# Slave_Device.net
KiCad netlist of a schematic drawn in EAGLE
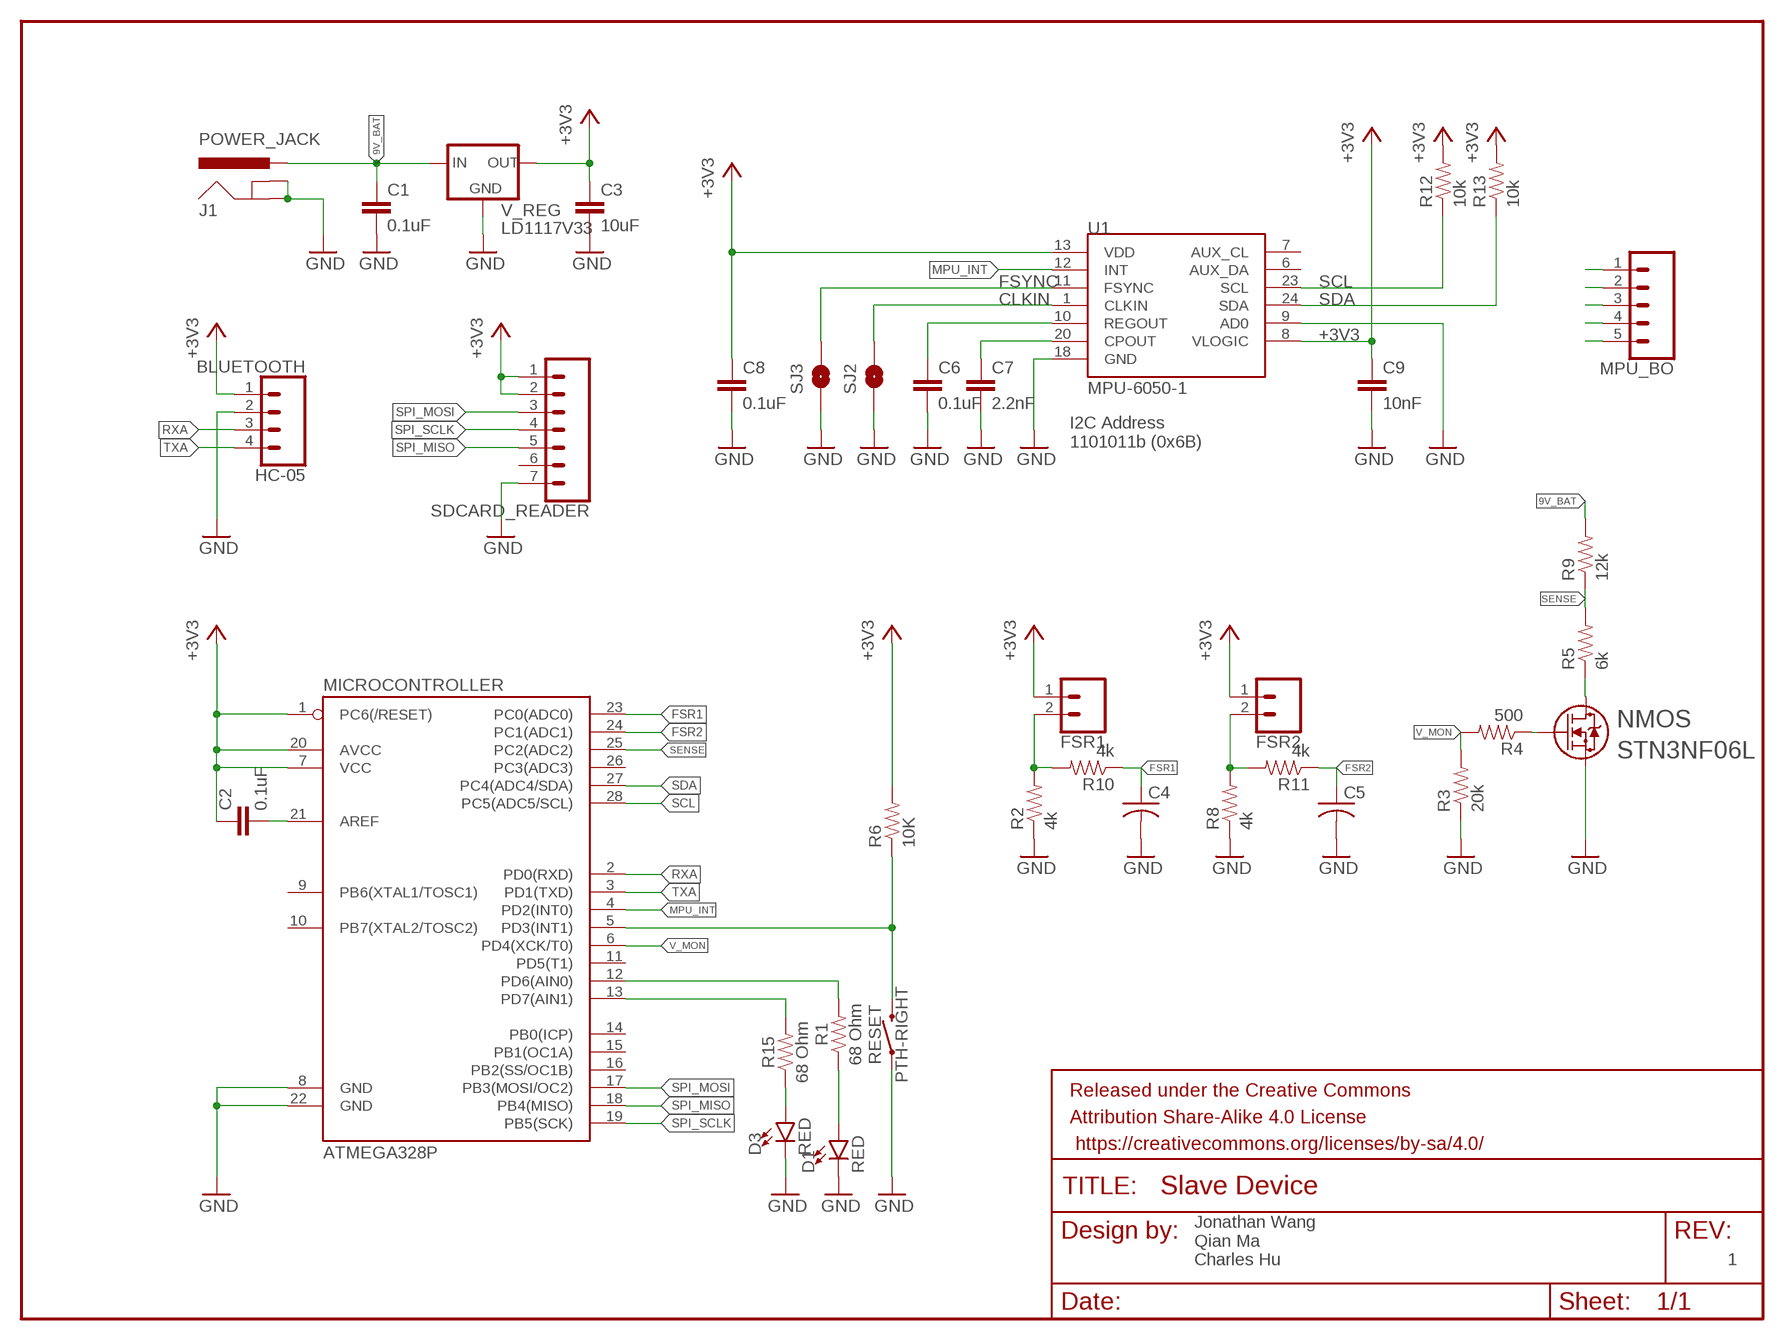
[diagram p0: schematic, sheet 1]

(export (version "E")
  (design (tool "Eeschema 10.0.6"))
  (components
    (comp (ref "C1")
      (value "0.1uF")
      (footprint "eagle-import:0603-CAP")
      (libsource (lib "eagle-import") (part "CAP0603-CAP"))
    )
    (comp (ref "C2")
      (value "0.1uF")
      (footprint "eagle-import:0603-CAP")
      (libsource (lib "eagle-import") (part "CAP0603-CAP"))
    )
    (comp (ref "C3")
      (value "10uF")
      (footprint "eagle-import:0603-CAP")
      (libsource (lib "eagle-import") (part "CAP0603-CAP"))
    )
    (comp (ref "C4")
      (value "C-US050-050X075")
      (footprint "eagle-import:C050-050X075")
      (libsource (lib "eagle-import") (part "C-US050-050X075"))
    )
    (comp (ref "C5")
      (value "C-US050-050X075")
      (footprint "eagle-import:C050-050X075")
      (libsource (lib "eagle-import") (part "C-US050-050X075"))
    )
    (comp (ref "C6")
      (value "0.1uF")
      (footprint "eagle-import:0603-CAP")
      (libsource (lib "eagle-import") (part "CAP0603-CAP"))
    )
    (comp (ref "C7")
      (value "2.2nF")
      (footprint "eagle-import:0603-CAP")
      (libsource (lib "eagle-import") (part "CAP0603-CAP"))
    )
    (comp (ref "C8")
      (value "0.1uF")
      (footprint "eagle-import:0603-CAP")
      (libsource (lib "eagle-import") (part "CAP0603-CAP"))
    )
    (comp (ref "C9")
      (value "10nF")
      (footprint "eagle-import:0603-CAP")
      (libsource (lib "eagle-import") (part "CAP0603-CAP"))
    )
    (comp (ref "D1")
      (value "RED")
      (footprint "eagle-import:LED_3MM")
      (libsource (lib "eagle-import") (part "LED3MM"))
    )
    (comp (ref "D3")
      (value "RED")
      (footprint "eagle-import:LED_3MM")
      (libsource (lib "eagle-import") (part "LED3MM"))
    )
    (comp (ref "FRAME1")
      (value "FRAME-LETTERNO_PACKAGE")
      (footprint "eagle-import:DUMMY")
      (fields (field (name "DESIGNER") "Nobody"))
      (libsource (lib "eagle-import") (part "FRAME-LETTERNO_PACKAGE"))
    )
    (comp (ref "FSR1")
      (value "CONN_02")
      (footprint "eagle-import:1X02")
      (libsource (lib "eagle-import") (part "CONN_02"))
    )
    (comp (ref "FSR2")
      (value "CONN_02")
      (footprint "eagle-import:1X02")
      (libsource (lib "eagle-import") (part "CONN_02"))
    )
    (comp (ref "HC-05")
      (value "BLUETOOTH")
      (footprint "eagle-import:1X04")
      (libsource (lib "eagle-import") (part "CONN_04"))
    )
    (comp (ref "J1")
      (value "POWER_JACK")
      (footprint "eagle-import:POWER_JACK_PTH")
      (libsource (lib "eagle-import") (part "POWER_JACK"))
    )
    (comp (ref "MICROCONTROLLER")
      (value "ATMEGA328P")
      (footprint "eagle-import:DIP28")
      (libsource (lib "eagle-import") (part "ATMEGA328P_PDIP"))
    )
    (comp (ref "MPU_BO")
      (value "CONN_05")
      (footprint "eagle-import:1X05")
      (libsource (lib "eagle-import") (part "CONN_05"))
    )
    (comp (ref "NMOS")
      (value "STN3NF06L")
      (footprint "eagle-import:SOT-223")
      (libsource (lib "eagle-import") (part "STN3NF06L"))
    )
    (comp (ref "R1")
      (value "68 Ohm")
      (footprint "eagle-import:0603")
      (libsource (lib "eagle-import") (part "68OHM-0603-1/10W-1%"))
    )
    (comp (ref "R2")
      (value "4k")
      (footprint "eagle-import:0603-RES")
      (libsource (lib "eagle-import") (part "10KOHM-1/10W-1%(0603)0603"))
    )
    (comp (ref "R3")
      (value "20k")
      (footprint "eagle-import:0603-RES")
      (libsource (lib "eagle-import") (part "10KOHM-1/10W-1%(0603)0603"))
    )
    (comp (ref "R4")
      (value "500")
      (footprint "eagle-import:0603-RES")
      (libsource (lib "eagle-import") (part "10KOHM-1/10W-1%(0603)0603"))
    )
    (comp (ref "R5")
      (value "6k")
      (footprint "eagle-import:0603-RES")
      (libsource (lib "eagle-import") (part "10KOHM-1/10W-1%(0603)0603"))
    )
    (comp (ref "R6")
      (value "10K")
      (footprint "eagle-import:0603-RES")
      (libsource (lib "eagle-import") (part "10KOHM-1/10W-1%(0603)0603"))
    )
    (comp (ref "R8")
      (value "4k")
      (footprint "eagle-import:0603-RES")
      (libsource (lib "eagle-import") (part "10KOHM-1/10W-1%(0603)0603"))
    )
    (comp (ref "R9")
      (value "12k")
      (footprint "eagle-import:0603-RES")
      (libsource (lib "eagle-import") (part "10KOHM-1/10W-1%(0603)0603"))
    )
    (comp (ref "R10")
      (value "4k")
      (footprint "eagle-import:0603-RES")
      (libsource (lib "eagle-import") (part "10KOHM-1/10W-1%(0603)0603"))
    )
    (comp (ref "R11")
      (value "4k")
      (footprint "eagle-import:0603-RES")
      (libsource (lib "eagle-import") (part "10KOHM-1/10W-1%(0603)0603"))
    )
    (comp (ref "R12")
      (value "10k")
      (footprint "eagle-import:0603-RES")
      (libsource (lib "eagle-import") (part "RESISTOR0603-RES"))
    )
    (comp (ref "R13")
      (value "10k")
      (footprint "eagle-import:0603-RES")
      (libsource (lib "eagle-import") (part "RESISTOR0603-RES"))
    )
    (comp (ref "R15")
      (value "68 Ohm")
      (footprint "eagle-import:0603")
      (libsource (lib "eagle-import") (part "68OHM-0603-1/10W-1%"))
    )
    (comp (ref "RESET")
      (value "PTH-RIGHT")
      (footprint "eagle-import:TACTILE_SWITCH_PTH_RIGHT_ANGLE_KIT")
      (libsource (lib "eagle-import") (part "MOMENTARY-SWITCH-SPST-PTH-RIGHT-ANGLE-KIT"))
    )
    (comp (ref "SDCARD_READER")
      (value "CONN_07")
      (footprint "eagle-import:1X07")
      (libsource (lib "eagle-import") (part "CONN_07"))
    )
    (comp (ref "SJ2")
      (value "SOLDERJUMPERTRACE")
      (footprint "eagle-import:SJ_2S-TRACE")
      (libsource (lib "eagle-import") (part "SOLDERJUMPERTRACE"))
    )
    (comp (ref "SJ3")
      (value "SOLDERJUMPERTRACE")
      (footprint "eagle-import:SJ_2S-TRACE")
      (libsource (lib "eagle-import") (part "SOLDERJUMPERTRACE"))
    )
    (comp (ref "U1")
      (value "MPU-6050-1")
      (footprint "eagle-import:QFN-24-4MM2")
      (libsource (lib "eagle-import") (part "MPU-6050-1"))
    )
    (comp (ref "V_REG")
      (value "LD1117V33")
      (footprint "eagle-import:78XXL")
      (libsource (lib "eagle-import") (part "V_REG_LD1117VXX"))
    )
  )
  (nets
    (net (code "1") (name "+3V3") (class "Default")
      (node (ref "C2") (pin "1") (pinfunction "1_1") (pintype "passive"))
      (node (ref "C3") (pin "1") (pinfunction "1_1") (pintype "passive"))
      (node (ref "C8") (pin "1") (pinfunction "1_1") (pintype "passive"))
      (node (ref "C9") (pin "1") (pinfunction "1_1") (pintype "passive"))
      (node (ref "FSR1") (pin "1") (pinfunction "1_1") (pintype "passive"))
      (node (ref "FSR2") (pin "1") (pinfunction "1_1") (pintype "passive"))
      (node (ref "HC-05") (pin "1") (pinfunction "1_1") (pintype "passive"))
      (node (ref "MICROCONTROLLER") (pin "1") (pinfunction "PC6(/RESET)_1") (pintype "bidirectional"))
      (node (ref "MICROCONTROLLER") (pin "20") (pinfunction "AVCC_20") (pintype "bidirectional"))
      (node (ref "MICROCONTROLLER") (pin "7") (pinfunction "VCC_7") (pintype "bidirectional"))
      (node (ref "MPU_BO") (pin "5") (pinfunction "5_5") (pintype "passive"))
      (node (ref "R12") (pin "2") (pinfunction "2_2") (pintype "passive"))
      (node (ref "R13") (pin "2") (pinfunction "2_2") (pintype "passive"))
      (node (ref "R6") (pin "2") (pinfunction "2_2") (pintype "passive"))
      (node (ref "SDCARD_READER") (pin "1") (pinfunction "1_1") (pintype "passive"))
      (node (ref "SDCARD_READER") (pin "2") (pinfunction "2_2") (pintype "passive"))
      (node (ref "U1") (pin "13") (pinfunction "VDD_13") (pintype "bidirectional"))
      (node (ref "U1") (pin "8") (pinfunction "VLOGIC_8") (pintype "bidirectional"))
      (node (ref "V_REG") (pin "GND") (pinfunction "OUT_GND") (pintype "passive"))
    )
    (net (code "2") (name "/CLKIN") (class "Default")
      (node (ref "SJ2") (pin "2") (pinfunction "2_2") (pintype "passive"))
      (node (ref "U1") (pin "1") (pinfunction "CLKIN_1") (pintype "bidirectional"))
    )
    (net (code "3") (name "/FSYNC") (class "Default")
      (node (ref "SJ3") (pin "2") (pinfunction "2_2") (pintype "passive"))
      (node (ref "U1") (pin "11") (pinfunction "FSYNC_11") (pintype "bidirectional"))
    )
    (net (code "4") (name "9V_BAT") (class "Default")
      (node (ref "C1") (pin "1") (pinfunction "1_1") (pintype "passive"))
      (node (ref "J1") (pin "PWR") (pinfunction "PWR_PWR") (pintype "bidirectional"))
      (node (ref "R9") (pin "2") (pinfunction "2_2") (pintype "passive"))
      (node (ref "V_REG") (pin "OUT") (pinfunction "IN_OUT") (pintype "input"))
    )
    (net (code "5") (name "FSR1") (class "Default")
      (node (ref "C4") (pin "1") (pinfunction "1_1") (pintype "passive"))
      (node (ref "MICROCONTROLLER") (pin "23") (pinfunction "PC0(ADC0)_23") (pintype "bidirectional"))
      (node (ref "R10") (pin "1") (pinfunction "1_1") (pintype "passive"))
    )
    (net (code "6") (name "FSR2") (class "Default")
      (node (ref "C5") (pin "1") (pinfunction "1_1") (pintype "passive"))
      (node (ref "MICROCONTROLLER") (pin "24") (pinfunction "PC1(ADC1)_24") (pintype "bidirectional"))
      (node (ref "R11") (pin "1") (pinfunction "1_1") (pintype "passive"))
    )
    (net (code "7") (name "GND") (class "Default")
      (node (ref "C1") (pin "2") (pinfunction "2_2") (pintype "passive"))
      (node (ref "C3") (pin "2") (pinfunction "2_2") (pintype "passive"))
      (node (ref "C4") (pin "2") (pinfunction "2_2") (pintype "passive"))
      (node (ref "C5") (pin "2") (pinfunction "2_2") (pintype "passive"))
      (node (ref "C6") (pin "2") (pinfunction "2_2") (pintype "passive"))
      (node (ref "C7") (pin "2") (pinfunction "2_2") (pintype "passive"))
      (node (ref "C8") (pin "2") (pinfunction "2_2") (pintype "passive"))
      (node (ref "C9") (pin "2") (pinfunction "2_2") (pintype "passive"))
      (node (ref "D1") (pin "K") (pinfunction "C_K") (pintype "passive"))
      (node (ref "D3") (pin "K") (pinfunction "C_K") (pintype "passive"))
      (node (ref "HC-05") (pin "2") (pinfunction "2_2") (pintype "passive"))
      (node (ref "J1") (pin "GND") (pinfunction "GND_GND") (pintype "bidirectional"))
      (node (ref "J1") (pin "GNDBREAK") (pinfunction "GNDBREAK_GNDBREAK") (pintype "bidirectional"))
      (node (ref "MICROCONTROLLER") (pin "22") (pinfunction "GND_22") (pintype "bidirectional"))
      (node (ref "MICROCONTROLLER") (pin "8") (pinfunction "GND_8") (pintype "bidirectional"))
      (node (ref "MPU_BO") (pin "4") (pinfunction "4_4") (pintype "passive"))
      (node (ref "NMOS") (pin "3") (pinfunction "3_3") (pintype "passive"))
      (node (ref "R2") (pin "1") (pinfunction "1_1") (pintype "passive"))
      (node (ref "R3") (pin "1") (pinfunction "1_1") (pintype "passive"))
      (node (ref "R8") (pin "1") (pinfunction "1_1") (pintype "passive"))
      (node (ref "RESET") (pin "1") (pinfunction "1_1") (pintype "passive"))
      (node (ref "SDCARD_READER") (pin "7") (pinfunction "7_7") (pintype "passive"))
      (node (ref "SJ2") (pin "1") (pinfunction "1_1") (pintype "passive"))
      (node (ref "SJ3") (pin "1") (pinfunction "1_1") (pintype "passive"))
      (node (ref "U1") (pin "18") (pinfunction "GND_18") (pintype "bidirectional"))
      (node (ref "U1") (pin "9") (pinfunction "AD0_9") (pintype "bidirectional"))
      (node (ref "V_REG") (pin "IN") (pinfunction "GND_IN") (pintype "input"))
    )
    (net (code "8") (name "MPU_INT") (class "Default")
      (node (ref "MICROCONTROLLER") (pin "4") (pinfunction "PD2(INT0)_4") (pintype "bidirectional"))
      (node (ref "MPU_BO") (pin "1") (pinfunction "1_1") (pintype "passive"))
      (node (ref "U1") (pin "12") (pinfunction "INT_12") (pintype "bidirectional"))
    )
    (net (code "9") (name "Net-(D1-PadA)") (class "Default")
      (node (ref "D1") (pin "A") (pinfunction "A_A") (pintype "passive"))
      (node (ref "R1") (pin "1") (pinfunction "1_1") (pintype "passive"))
    )
    (net (code "10") (name "Net-(D3-PadA)") (class "Default")
      (node (ref "D3") (pin "A") (pinfunction "A_A") (pintype "passive"))
      (node (ref "R15") (pin "1") (pinfunction "1_1") (pintype "passive"))
    )
    (net (code "11") (name "Net-(FSR1-Pad2)") (class "Default")
      (node (ref "FSR1") (pin "2") (pinfunction "2_2") (pintype "passive"))
      (node (ref "R10") (pin "2") (pinfunction "2_2") (pintype "passive"))
      (node (ref "R2") (pin "2") (pinfunction "2_2") (pintype "passive"))
    )
    (net (code "12") (name "Net-(FSR2-Pad2)") (class "Default")
      (node (ref "FSR2") (pin "2") (pinfunction "2_2") (pintype "passive"))
      (node (ref "R11") (pin "2") (pinfunction "2_2") (pintype "passive"))
      (node (ref "R8") (pin "2") (pinfunction "2_2") (pintype "passive"))
    )
    (net (code "13") (name "Net-(MICROCONTROLLER-AREF)") (class "Default")
      (node (ref "C2") (pin "2") (pinfunction "2_2") (pintype "passive"))
      (node (ref "MICROCONTROLLER") (pin "21") (pinfunction "AREF_21") (pintype "bidirectional"))
    )
    (net (code "14") (name "Net-(MICROCONTROLLER-PD3(INT1))") (class "Default")
      (node (ref "MICROCONTROLLER") (pin "5") (pinfunction "PD3(INT1)_5") (pintype "bidirectional"))
      (node (ref "R6") (pin "1") (pinfunction "1_1") (pintype "passive"))
      (node (ref "RESET") (pin "2") (pinfunction "2_2") (pintype "passive"))
    )
    (net (code "15") (name "Net-(MICROCONTROLLER-PD6(AIN0))") (class "Default")
      (node (ref "MICROCONTROLLER") (pin "12") (pinfunction "PD6(AIN0)_12") (pintype "bidirectional"))
      (node (ref "R1") (pin "2") (pinfunction "2_2") (pintype "passive"))
    )
    (net (code "16") (name "Net-(MICROCONTROLLER-PD7(AIN1))") (class "Default")
      (node (ref "MICROCONTROLLER") (pin "13") (pinfunction "PD7(AIN1)_13") (pintype "bidirectional"))
      (node (ref "R15") (pin "2") (pinfunction "2_2") (pintype "passive"))
    )
    (net (code "17") (name "Net-(NMOS-Pad1)") (class "Default")
      (node (ref "NMOS") (pin "1") (pinfunction "1_1") (pintype "passive"))
      (node (ref "R4") (pin "1") (pinfunction "1_1") (pintype "passive"))
    )
    (net (code "18") (name "Net-(NMOS-Pad2)") (class "Default")
      (node (ref "NMOS") (pin "2") (pinfunction "2_2") (pintype "passive"))
      (node (ref "R5") (pin "1") (pinfunction "1_1") (pintype "passive"))
    )
    (net (code "19") (name "Net-(U1-CPOUT)") (class "Default")
      (node (ref "C7") (pin "1") (pinfunction "1_1") (pintype "passive"))
      (node (ref "U1") (pin "20") (pinfunction "CPOUT_20") (pintype "bidirectional"))
    )
    (net (code "20") (name "Net-(U1-REGOUT)") (class "Default")
      (node (ref "C6") (pin "1") (pinfunction "1_1") (pintype "passive"))
      (node (ref "U1") (pin "10") (pinfunction "REGOUT_10") (pintype "bidirectional"))
    )
    (net (code "21") (name "RXA") (class "Default")
      (node (ref "HC-05") (pin "3") (pinfunction "3_3") (pintype "passive"))
      (node (ref "MICROCONTROLLER") (pin "2") (pinfunction "PD0(RXD)_2") (pintype "bidirectional"))
    )
    (net (code "22") (name "SCL") (class "Default")
      (node (ref "MICROCONTROLLER") (pin "28") (pinfunction "PC5(ADC5/SCL)_28") (pintype "bidirectional"))
      (node (ref "MPU_BO") (pin "2") (pinfunction "2_2") (pintype "passive"))
      (node (ref "R12") (pin "1") (pinfunction "1_1") (pintype "passive"))
      (node (ref "U1") (pin "23") (pinfunction "SCL_23") (pintype "bidirectional"))
    )
    (net (code "23") (name "SDA") (class "Default")
      (node (ref "MICROCONTROLLER") (pin "27") (pinfunction "PC4(ADC4/SDA)_27") (pintype "bidirectional"))
      (node (ref "MPU_BO") (pin "3") (pinfunction "3_3") (pintype "passive"))
      (node (ref "R13") (pin "1") (pinfunction "1_1") (pintype "passive"))
      (node (ref "U1") (pin "24") (pinfunction "SDA_24") (pintype "bidirectional"))
    )
    (net (code "24") (name "SENSE") (class "Default")
      (node (ref "MICROCONTROLLER") (pin "25") (pinfunction "PC2(ADC2)_25") (pintype "bidirectional"))
      (node (ref "R5") (pin "2") (pinfunction "2_2") (pintype "passive"))
      (node (ref "R9") (pin "1") (pinfunction "1_1") (pintype "passive"))
    )
    (net (code "25") (name "SPI_MISO") (class "Default")
      (node (ref "MICROCONTROLLER") (pin "18") (pinfunction "PB4(MISO)_18") (pintype "bidirectional"))
      (node (ref "SDCARD_READER") (pin "5") (pinfunction "5_5") (pintype "passive"))
    )
    (net (code "26") (name "SPI_MOSI") (class "Default")
      (node (ref "MICROCONTROLLER") (pin "17") (pinfunction "PB3(MOSI/OC2)_17") (pintype "bidirectional"))
      (node (ref "SDCARD_READER") (pin "3") (pinfunction "3_3") (pintype "passive"))
    )
    (net (code "27") (name "SPI_SCLK") (class "Default")
      (node (ref "MICROCONTROLLER") (pin "19") (pinfunction "PB5(SCK)_19") (pintype "bidirectional"))
      (node (ref "SDCARD_READER") (pin "4") (pinfunction "4_4") (pintype "passive"))
    )
    (net (code "28") (name "TXA") (class "Default")
      (node (ref "HC-05") (pin "4") (pinfunction "4_4") (pintype "passive"))
      (node (ref "MICROCONTROLLER") (pin "3") (pinfunction "PD1(TXD)_3") (pintype "bidirectional"))
    )
    (net (code "29") (name "V_MON") (class "Default")
      (node (ref "MICROCONTROLLER") (pin "6") (pinfunction "PD4(XCK/T0)_6") (pintype "bidirectional"))
      (node (ref "R3") (pin "2") (pinfunction "2_2") (pintype "passive"))
      (node (ref "R4") (pin "2") (pinfunction "2_2") (pintype "passive"))
    )
    (net (code "30") (name "unconnected-(MICROCONTROLLER-PB0(ICP)-Pad14)") (class "Default")
      (node (ref "MICROCONTROLLER") (pin "14") (pinfunction "PB0(ICP)_14") (pintype "bidirectional"))
    )
    (net (code "31") (name "unconnected-(MICROCONTROLLER-PB1(OC1A)-Pad15)") (class "Default")
      (node (ref "MICROCONTROLLER") (pin "15") (pinfunction "PB1(OC1A)_15") (pintype "bidirectional"))
    )
    (net (code "32") (name "unconnected-(MICROCONTROLLER-PB2(SS{slash}OC1B)-Pad16)") (class "Default")
      (node (ref "MICROCONTROLLER") (pin "16") (pinfunction "PB2(SS/OC1B)_16") (pintype "bidirectional"))
    )
    (net (code "33") (name "unconnected-(MICROCONTROLLER-PB6(XTAL1{slash}TOSC1)-Pad9)") (class "Default")
      (node (ref "MICROCONTROLLER") (pin "9") (pinfunction "PB6(XTAL1/TOSC1)_9") (pintype "bidirectional"))
    )
    (net (code "34") (name "unconnected-(MICROCONTROLLER-PB7(XTAL2{slash}TOSC2)-Pad10)") (class "Default")
      (node (ref "MICROCONTROLLER") (pin "10") (pinfunction "PB7(XTAL2/TOSC2)_10") (pintype "bidirectional"))
    )
    (net (code "35") (name "unconnected-(MICROCONTROLLER-PC3(ADC3)-Pad26)") (class "Default")
      (node (ref "MICROCONTROLLER") (pin "26") (pinfunction "PC3(ADC3)_26") (pintype "bidirectional"))
    )
    (net (code "36") (name "unconnected-(MICROCONTROLLER-PD5(T1)-Pad11)") (class "Default")
      (node (ref "MICROCONTROLLER") (pin "11") (pinfunction "PD5(T1)_11") (pintype "bidirectional"))
    )
    (net (code "37") (name "unconnected-(SDCARD_READER-Pad6)") (class "Default")
      (node (ref "SDCARD_READER") (pin "6") (pinfunction "6_6") (pintype "passive"))
    )
    (net (code "38") (name "unconnected-(U1-AUX_CL-Pad7)") (class "Default")
      (node (ref "U1") (pin "7") (pinfunction "AUX_CL_7") (pintype "bidirectional"))
    )
    (net (code "39") (name "unconnected-(U1-AUX_DA-Pad6)") (class "Default")
      (node (ref "U1") (pin "6") (pinfunction "AUX_DA_6") (pintype "bidirectional"))
    )
  )
)
